# Supply.net
KiCad netlist of a schematic drawn in Altium Designer
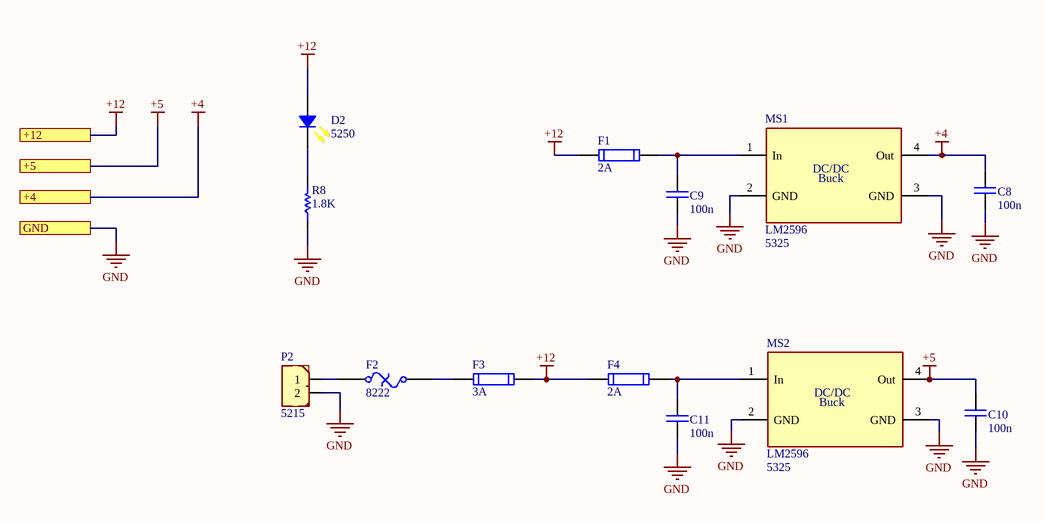
[diagram p0: Supply.SchDoc]

(export (version "E")
  (design (tool "Eeschema 10.0.6"))
  (components
    (comp (ref "C8")
      (value "100n")
      (footprint "CAP 1206/3216")
      (description "Bipolar ceramic capacitor SMD")
      (fields (field (name "VALIDATION") "Valid"))
      (libsource (lib "aKaReZa") (part "Cap_Multi_SMD_100nF_1206"))
    )
    (comp (ref "C9")
      (value "100n")
      (footprint "CAP 1206/3216")
      (description "Bipolar ceramic capacitor SMD")
      (fields (field (name "VALIDATION") "Valid"))
      (libsource (lib "aKaReZa") (part "Cap_Multi_SMD_100nF_1206"))
    )
    (comp (ref "C10")
      (value "100n")
      (footprint "CAP 1206/3216")
      (description "Bipolar ceramic capacitor SMD")
      (fields (field (name "VALIDATION") "Valid"))
      (libsource (lib "aKaReZa") (part "Cap_Multi_SMD_100nF_1206"))
    )
    (comp (ref "C11")
      (value "100n")
      (footprint "CAP 1206/3216")
      (description "Bipolar ceramic capacitor SMD")
      (fields (field (name "VALIDATION") "Valid"))
      (libsource (lib "aKaReZa") (part "Cap_Multi_SMD_100nF_1206"))
    )
    (comp (ref "D2")
      (value "Yellow, 1206")
      (footprint "LED 1206/3216 YELLOW")
      (description "LED")
      (fields (field (name "INFLOW") "5250") (field (name "VALIDATION") "Valid"))
      (libsource (lib "aKaReZa") (part "Semi_LED_Yellow_1206"))
    )
    (comp (ref "F1")
      (value "2A")
      (footprint "1206_F")
      (description "Short circiut  protection")
      (fields (field (name "VALIDATION") "Valid"))
      (libsource (lib "aKaReZa") (part "Other_Elec_Fuse_SMD"))
    )
    (comp (ref "F2")
      (value "180'C, 10'A")
      (footprint "PIN-W2/E2.8")
      (description "Thermal Fuse")
      (fields (field (name "INFLOW") "8222") (field (name "VALIDATION") "NT"))
      (libsource (lib "aKaReZa") (part "Other_Elec_Fuse_Thermal"))
    )
    (comp (ref "F3")
      (value "3A")
      (footprint "1206_F")
      (description "Short circiut  protection")
      (fields (field (name "VALIDATION") "Valid"))
      (libsource (lib "aKaReZa") (part "Other_Elec_Fuse_SMD"))
    )
    (comp (ref "F4")
      (value "2A")
      (footprint "1206_F")
      (description "Short circiut  protection")
      (fields (field (name "VALIDATION") "Valid"))
      (libsource (lib "aKaReZa") (part "Other_Elec_Fuse_SMD"))
    )
    (comp (ref "MS1")
      (value "LM2596")
      (footprint "LM2596_modsen")
      (description "DC to DC Buck converter 1.23V-30V 3A")
      (fields (field (name "INFLOW") "5325") (field (name "VALIDATION") "Valid"))
      (libsource (lib "aKaReZa") (part "ModSen_LM2596"))
    )
    (comp (ref "MS2")
      (value "LM2596")
      (footprint "LM2596_modsen")
      (description "DC to DC Buck converter 1.23V-30V 3A")
      (fields (field (name "INFLOW") "5325") (field (name "VALIDATION") "Valid"))
      (libsource (lib "aKaReZa") (part "ModSen_LM2596"))
    )
    (comp (ref "P2")
      (value "2'Pin")
      (footprint "645002117322")
      (description "2'Pin Power Connector")
      (fields (field (name "INFLOW") "5215") (field (name "VALIDATION") "Valid"))
      (libsource (lib "aKaReZa") (part "Con_Power_2_PC_H"))
    )
    (comp (ref "R8")
      (value "1.8K")
      (footprint "RES 1206 (3216X08L)")
      (description "Resistor")
      (fields (field (name "VALIDATION") "Valid"))
      (libsource (lib "aKaReZa") (part "Res_SMD_1206"))
    )
  )
  (nets
    (net (code "1") (name "+4") (class "Default")
      (node (ref "C8") (pin "1") (pinfunction "1_1") (pintype "passive"))
      (node (ref "MS1") (pin "4") (pinfunction "Out_4") (pintype "power_in"))
    )
    (net (code "2") (name "+5") (class "Default")
      (node (ref "C10") (pin "1") (pinfunction "1_1") (pintype "passive"))
      (node (ref "MS2") (pin "4") (pinfunction "Out_4") (pintype "power_in"))
    )
    (net (code "3") (name "+12") (class "Default")
      (node (ref "D2") (pin "1") (pinfunction "1_1") (pintype "passive"))
      (node (ref "F1") (pin "1") (pinfunction "1_1") (pintype "passive"))
      (node (ref "F3") (pin "2") (pinfunction "2_2") (pintype "passive"))
      (node (ref "F4") (pin "1") (pinfunction "1_1") (pintype "passive"))
    )
    (net (code "4") (name "GND") (class "Default")
      (node (ref "C10") (pin "2") (pinfunction "2_2") (pintype "passive"))
      (node (ref "C11") (pin "2") (pinfunction "2_2") (pintype "passive"))
      (node (ref "C8") (pin "2") (pinfunction "2_2") (pintype "passive"))
      (node (ref "C9") (pin "2") (pinfunction "2_2") (pintype "passive"))
      (node (ref "MS1") (pin "2") (pinfunction "GND_2") (pintype "power_in"))
      (node (ref "MS1") (pin "3") (pinfunction "GND_3") (pintype "power_in"))
      (node (ref "MS2") (pin "2") (pinfunction "GND_2") (pintype "power_in"))
      (node (ref "MS2") (pin "3") (pinfunction "GND_3") (pintype "power_in"))
      (node (ref "P2") (pin "2") (pinfunction "2_2") (pintype "passive"))
      (node (ref "R8") (pin "1") (pinfunction "1_1") (pintype "passive"))
    )
    (net (code "5") (name "Net-(D2-Pad2)") (class "Default")
      (node (ref "D2") (pin "2") (pinfunction "2_2") (pintype "passive"))
      (node (ref "R8") (pin "2") (pinfunction "2_2") (pintype "passive"))
    )
    (net (code "6") (name "Net-(F2-Pad1)") (class "Default")
      (node (ref "F2") (pin "1") (pinfunction "1_1") (pintype "passive"))
      (node (ref "P2") (pin "1") (pinfunction "1_1") (pintype "passive"))
    )
    (net (code "7") (name "Net-(F2-Pad2)") (class "Default")
      (node (ref "F2") (pin "2") (pinfunction "2_2") (pintype "passive"))
      (node (ref "F3") (pin "1") (pinfunction "1_1") (pintype "passive"))
    )
    (net (code "8") (name "Net-(MS1-In)") (class "Default")
      (node (ref "C9") (pin "1") (pinfunction "1_1") (pintype "passive"))
      (node (ref "F1") (pin "2") (pinfunction "2_2") (pintype "passive"))
      (node (ref "MS1") (pin "1") (pinfunction "In_1") (pintype "power_in"))
    )
    (net (code "9") (name "Net-(MS2-In)") (class "Default")
      (node (ref "C11") (pin "1") (pinfunction "1_1") (pintype "passive"))
      (node (ref "F4") (pin "2") (pinfunction "2_2") (pintype "passive"))
      (node (ref "MS2") (pin "1") (pinfunction "In_1") (pintype "power_in"))
    )
  )
)
